# waga_can.net
KiCad netlist of a schematic drawn in EAGLE
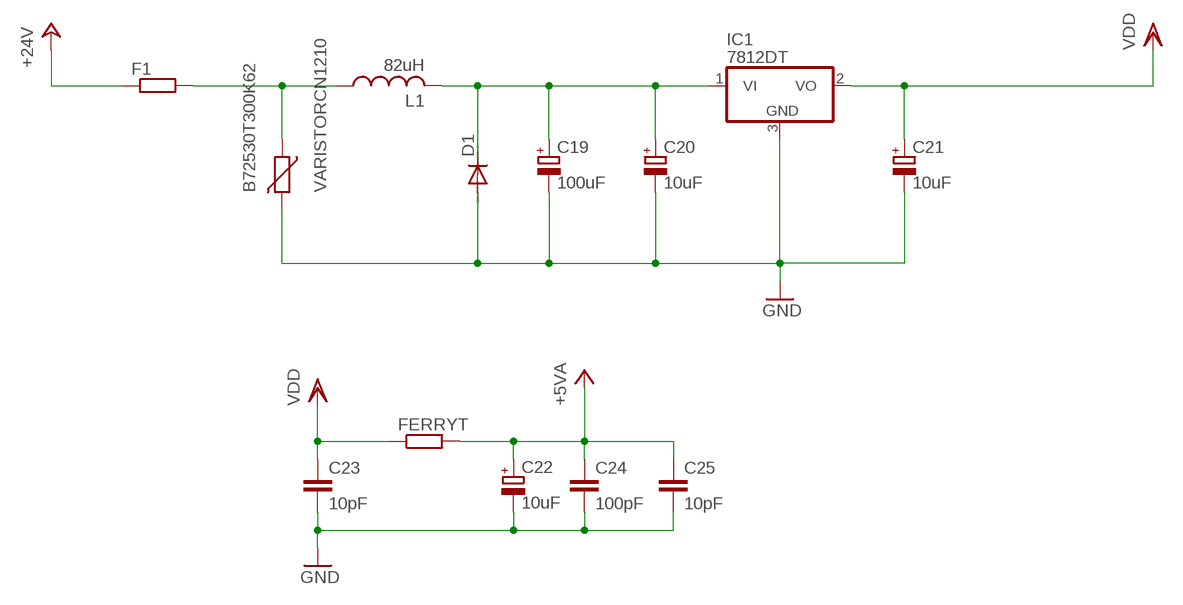
[diagram p0: schematic, sheet 1]
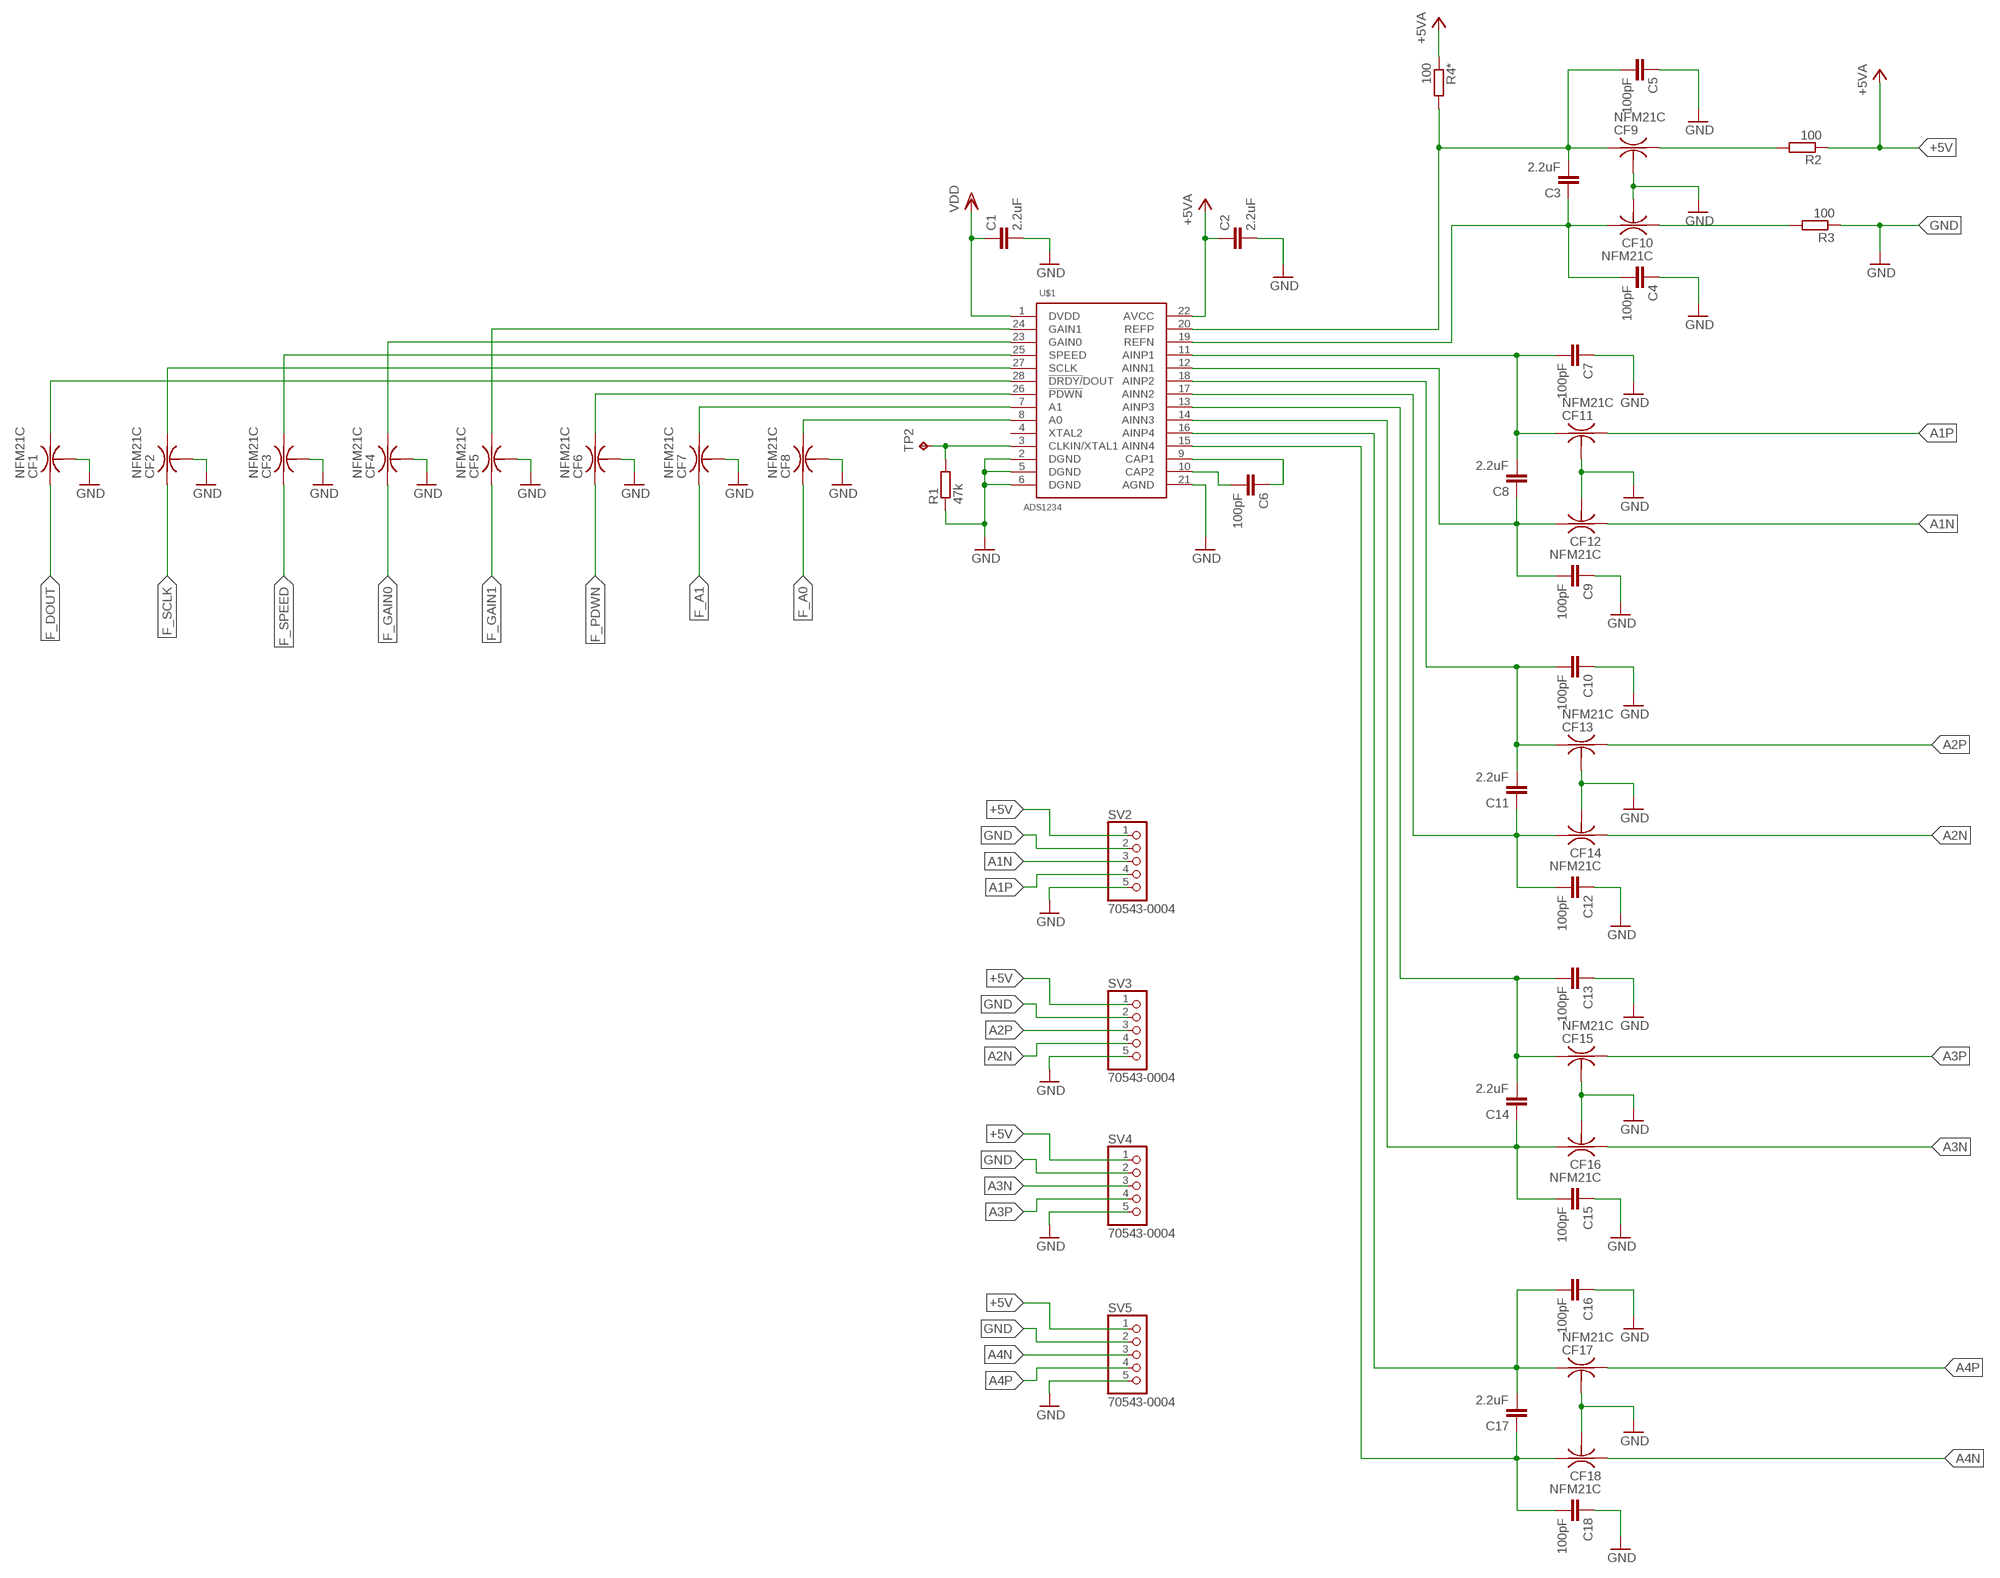
[diagram p1: schematic, sheet 2, part 1 of 2]
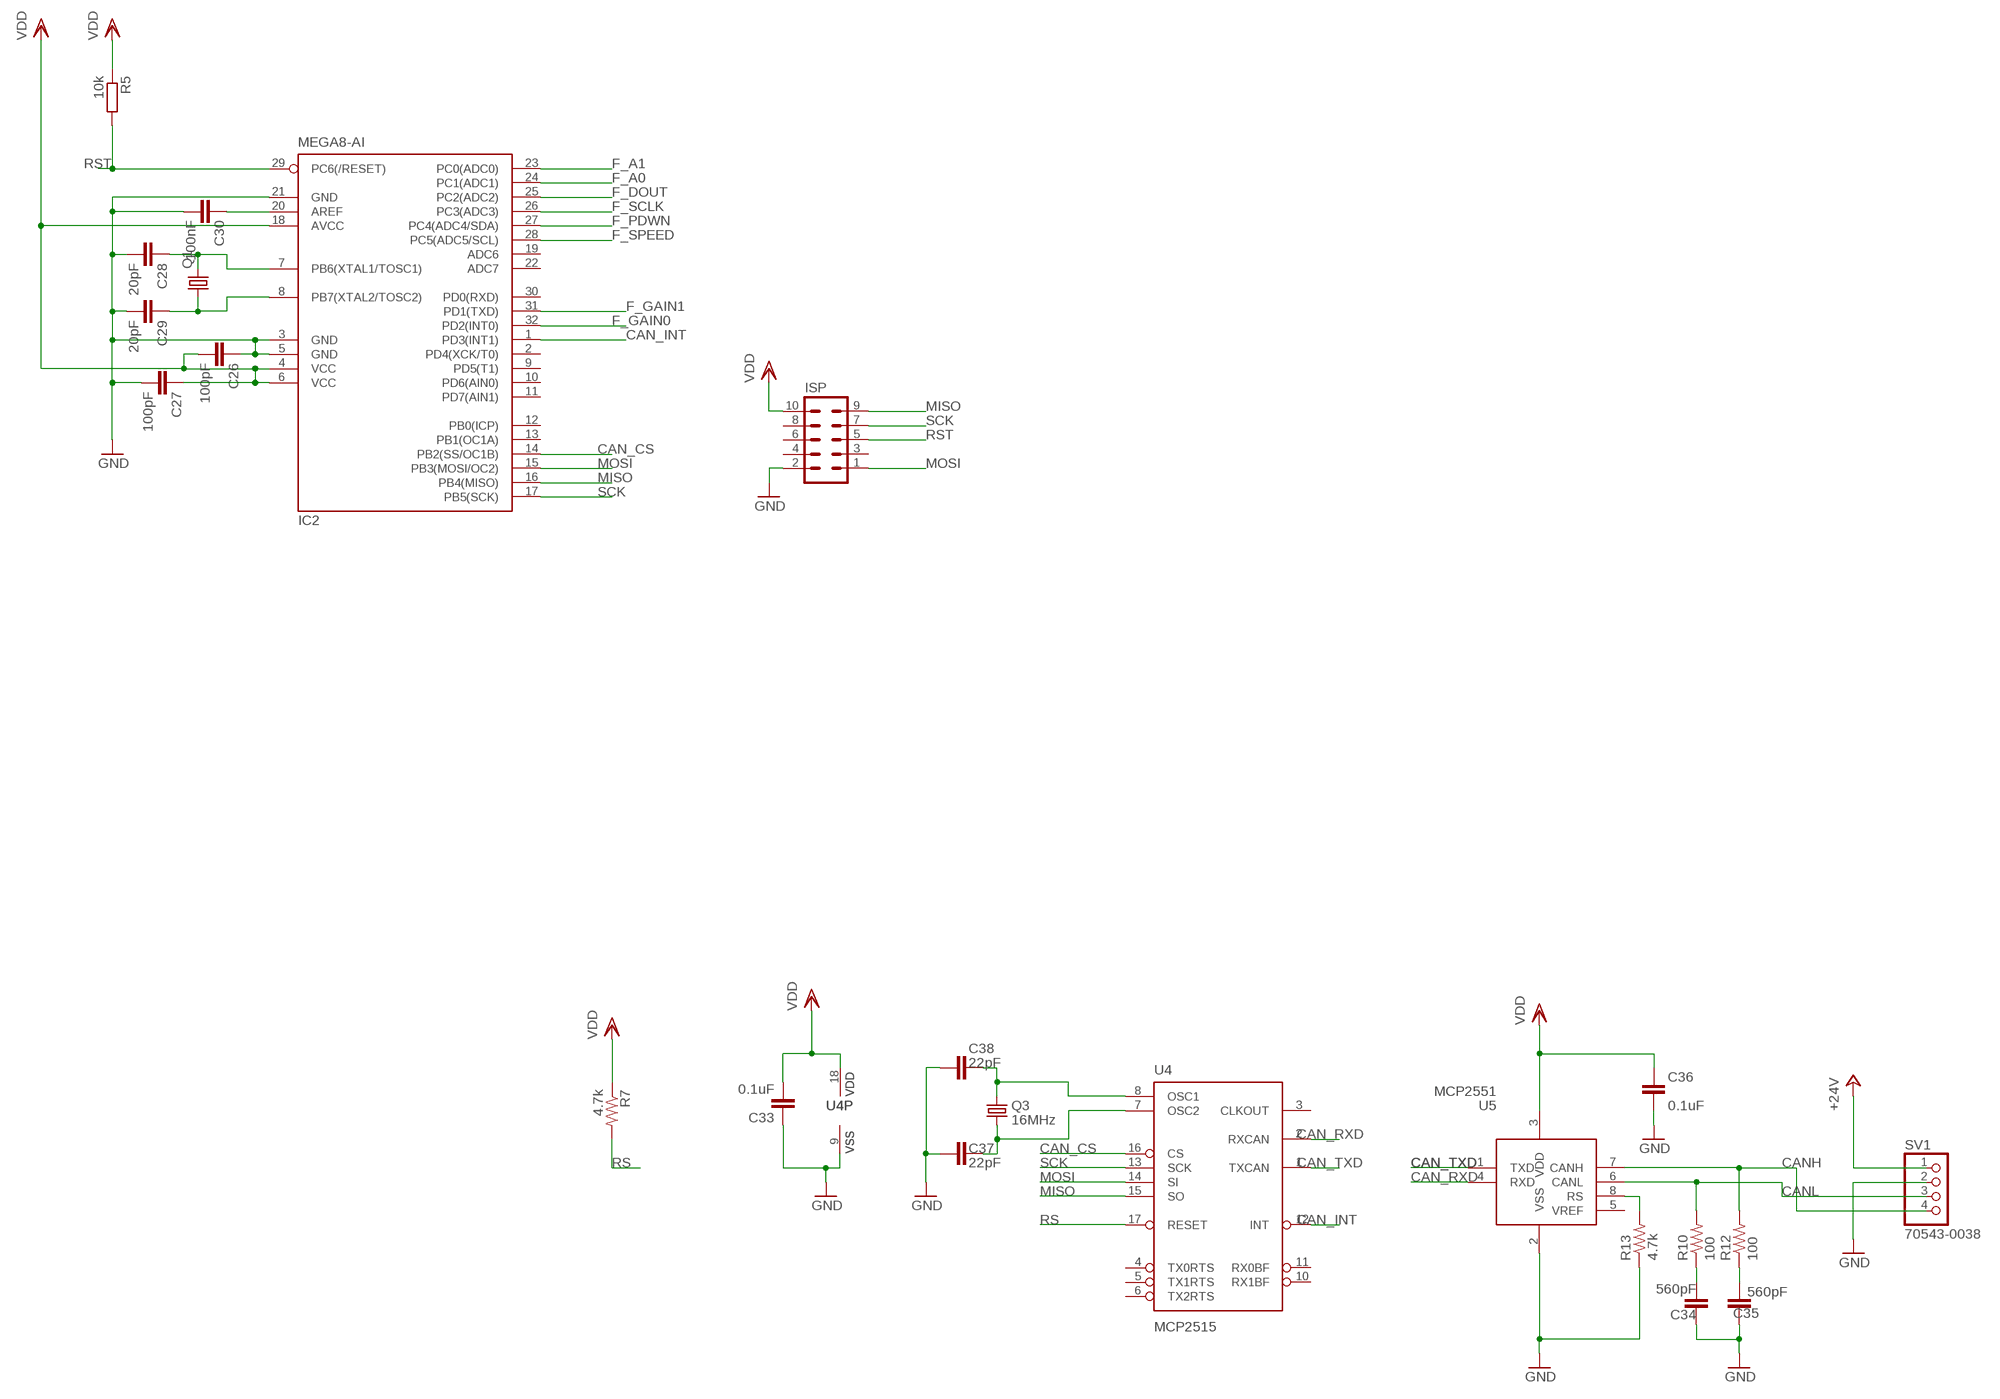
[diagram p2: schematic, sheet 2, part 2 of 2]

(export (version "E")
  (design (tool "Eeschema 10.0.6"))
  (components
    (comp (ref "B72530T300K62")
      (value "VARISTORCN1210")
      (footprint "eagle-import:CT_CN1210")
      (libsource (lib "eagle-import") (part "VARISTORCN1210"))
    )
    (comp (ref "C19")
      (value "100uF")
      (footprint "eagle-import:153CLV-0810")
      (libsource (lib "eagle-import") (part "CPOL-EU153CLV-0810"))
    )
    (comp (ref "C20")
      (value "10uF")
      (footprint "eagle-import:153CLV-0605")
      (libsource (lib "eagle-import") (part "CPOL-EU153CLV-0605"))
    )
    (comp (ref "C21")
      (value "10uF")
      (footprint "eagle-import:153CLV-0605")
      (libsource (lib "eagle-import") (part "CPOL-EU153CLV-0605"))
    )
    (comp (ref "C22")
      (value "10uF")
      (footprint "eagle-import:153CLV-0605")
      (libsource (lib "eagle-import") (part "CPOL-EU153CLV-0605"))
    )
    (comp (ref "C23")
      (value "10pF")
      (footprint "eagle-import:C0805")
      (libsource (lib "eagle-import") (part "C-EUC0805"))
    )
    (comp (ref "C24")
      (value "100pF")
      (footprint "eagle-import:C0805")
      (libsource (lib "eagle-import") (part "C-EUC0805"))
    )
    (comp (ref "C25")
      (value "10pF")
      (footprint "eagle-import:C0805")
      (libsource (lib "eagle-import") (part "C-EUC0805"))
    )
    (comp (ref "D1")
      (value "DIODE-SMB")
      (footprint "eagle-import:SMB")
      (libsource (lib "eagle-import") (part "DIODE-SMB"))
    )
    (comp (ref "F1")
      (value "R-EU_1812X7R")
      (footprint "eagle-import:1812X7R")
      (libsource (lib "eagle-import") (part "R-EU_1812X7R"))
    )
    (comp (ref "FERRYT")
      (value "R-EU_M0805")
      (footprint "eagle-import:M0805")
      (libsource (lib "eagle-import") (part "R-EU_M0805"))
    )
    (comp (ref "IC1")
      (value "7812DT")
      (footprint "eagle-import:TO252")
      (libsource (lib "eagle-import") (part "78DT12"))
    )
    (comp (ref "L1")
      (value "82uH")
      (footprint "eagle-import:L4532P")
      (libsource (lib "eagle-import") (part "L-USL4532P"))
    )
    (comp (ref "C1")
      (value "2.2uF")
      (footprint "eagle-import:C0805K")
      (libsource (lib "eagle-import") (part "C-EUC0805K"))
    )
    (comp (ref "C2")
      (value "2.2uF")
      (footprint "eagle-import:C0805K")
      (libsource (lib "eagle-import") (part "C-EUC0805K"))
    )
    (comp (ref "C3")
      (value "2.2uF")
      (footprint "eagle-import:C0805K")
      (libsource (lib "eagle-import") (part "C-EUC0805K"))
    )
    (comp (ref "C4")
      (value "100pF")
      (footprint "eagle-import:C0603")
      (libsource (lib "eagle-import") (part "C-EUC0603"))
    )
    (comp (ref "C5")
      (value "100pF")
      (footprint "eagle-import:C0603")
      (libsource (lib "eagle-import") (part "C-EUC0603"))
    )
    (comp (ref "C6")
      (value "100pF")
      (footprint "eagle-import:C0603")
      (libsource (lib "eagle-import") (part "C-EUC0603"))
    )
    (comp (ref "C7")
      (value "100pF")
      (footprint "eagle-import:C0603")
      (libsource (lib "eagle-import") (part "C-EUC0603"))
    )
    (comp (ref "C8")
      (value "2.2uF")
      (footprint "eagle-import:C0805K")
      (libsource (lib "eagle-import") (part "C-EUC0805K"))
    )
    (comp (ref "C9")
      (value "100pF")
      (footprint "eagle-import:C0603")
      (libsource (lib "eagle-import") (part "C-EUC0603"))
    )
    (comp (ref "C10")
      (value "100pF")
      (footprint "eagle-import:C0603")
      (libsource (lib "eagle-import") (part "C-EUC0603"))
    )
    (comp (ref "C11")
      (value "2.2uF")
      (footprint "eagle-import:C0805K")
      (libsource (lib "eagle-import") (part "C-EUC0805K"))
    )
    (comp (ref "C12")
      (value "100pF")
      (footprint "eagle-import:C0603")
      (libsource (lib "eagle-import") (part "C-EUC0603"))
    )
    (comp (ref "C13")
      (value "100pF")
      (footprint "eagle-import:C0603")
      (libsource (lib "eagle-import") (part "C-EUC0603"))
    )
    (comp (ref "C14")
      (value "2.2uF")
      (footprint "eagle-import:C0805K")
      (libsource (lib "eagle-import") (part "C-EUC0805K"))
    )
    (comp (ref "C15")
      (value "100pF")
      (footprint "eagle-import:C0603")
      (libsource (lib "eagle-import") (part "C-EUC0603"))
    )
    (comp (ref "C16")
      (value "100pF")
      (footprint "eagle-import:C0603")
      (libsource (lib "eagle-import") (part "C-EUC0603"))
    )
    (comp (ref "C17")
      (value "2.2uF")
      (footprint "eagle-import:C0805K")
      (libsource (lib "eagle-import") (part "C-EUC0805K"))
    )
    (comp (ref "C18")
      (value "100pF")
      (footprint "eagle-import:C0603")
      (libsource (lib "eagle-import") (part "C-EUC0603"))
    )
    (comp (ref "C26")
      (value "100pF")
      (footprint "eagle-import:C0805K")
      (libsource (lib "eagle-import") (part "C-EUC0805K"))
    )
    (comp (ref "C27")
      (value "100pF")
      (footprint "eagle-import:C0805K")
      (libsource (lib "eagle-import") (part "C-EUC0805K"))
    )
    (comp (ref "C28")
      (value "20pF")
      (footprint "eagle-import:C0805K")
      (libsource (lib "eagle-import") (part "C-EUC0805K"))
    )
    (comp (ref "C29")
      (value "20pF")
      (footprint "eagle-import:C0805K")
      (libsource (lib "eagle-import") (part "C-EUC0805K"))
    )
    (comp (ref "C30")
      (value "100nF")
      (footprint "eagle-import:C0805K")
      (libsource (lib "eagle-import") (part "C-EUC0805K"))
    )
    (comp (ref "C33")
      (value "0.1uF")
      (footprint "eagle-import:0603-CAP")
      (libsource (lib "eagle-import") (part "CAP0603-CAP"))
    )
    (comp (ref "C34")
      (value "560pF")
      (footprint "eagle-import:0603-CAP")
      (libsource (lib "eagle-import") (part "CAP0603-CAP"))
    )
    (comp (ref "C35")
      (value "560pF")
      (footprint "eagle-import:0603-CAP")
      (libsource (lib "eagle-import") (part "CAP0603-CAP"))
    )
    (comp (ref "C36")
      (value "0.1uF")
      (footprint "eagle-import:0603-CAP")
      (libsource (lib "eagle-import") (part "CAP0603-CAP"))
    )
    (comp (ref "C37")
      (value "22pF")
      (footprint "eagle-import:0603-CAP")
      (libsource (lib "eagle-import") (part "CAP0603-CAP"))
    )
    (comp (ref "C38")
      (value "22pF")
      (footprint "eagle-import:0603-CAP")
      (libsource (lib "eagle-import") (part "CAP0603-CAP"))
    )
    (comp (ref "CF1")
      (value "NFM21C")
      (footprint "eagle-import:NFM21C")
      (fields (field (name "MPN") "NFM21CC102R1H3D"))
      (libsource (lib "eagle-import") (part "NFM21C"))
    )
    (comp (ref "CF2")
      (value "NFM21C")
      (footprint "eagle-import:NFM21C")
      (fields (field (name "MPN") "NFM21CC102R1H3D"))
      (libsource (lib "eagle-import") (part "NFM21C"))
    )
    (comp (ref "CF3")
      (value "NFM21C")
      (footprint "eagle-import:NFM21C")
      (fields (field (name "MPN") "NFM21CC102R1H3D"))
      (libsource (lib "eagle-import") (part "NFM21C"))
    )
    (comp (ref "CF4")
      (value "NFM21C")
      (footprint "eagle-import:NFM21C")
      (fields (field (name "MPN") "NFM21CC102R1H3D"))
      (libsource (lib "eagle-import") (part "NFM21C"))
    )
    (comp (ref "CF5")
      (value "NFM21C")
      (footprint "eagle-import:NFM21C")
      (fields (field (name "MPN") "NFM21CC102R1H3D"))
      (libsource (lib "eagle-import") (part "NFM21C"))
    )
    (comp (ref "CF6")
      (value "NFM21C")
      (footprint "eagle-import:NFM21C")
      (fields (field (name "MPN") "NFM21CC102R1H3D"))
      (libsource (lib "eagle-import") (part "NFM21C"))
    )
    (comp (ref "CF7")
      (value "NFM21C")
      (footprint "eagle-import:NFM21C")
      (fields (field (name "MPN") "NFM21CC102R1H3D"))
      (libsource (lib "eagle-import") (part "NFM21C"))
    )
    (comp (ref "CF8")
      (value "NFM21C")
      (footprint "eagle-import:NFM21C")
      (fields (field (name "MPN") "NFM21CC102R1H3D"))
      (libsource (lib "eagle-import") (part "NFM21C"))
    )
    (comp (ref "CF9")
      (value "NFM21C")
      (footprint "eagle-import:NFM21C")
      (fields (field (name "MPN") "NFM21CC102R1H3D"))
      (libsource (lib "eagle-import") (part "NFM21C"))
    )
    (comp (ref "CF10")
      (value "NFM21C")
      (footprint "eagle-import:NFM21C")
      (fields (field (name "MPN") "NFM21CC102R1H3D"))
      (libsource (lib "eagle-import") (part "NFM21C"))
    )
    (comp (ref "CF11")
      (value "NFM21C")
      (footprint "eagle-import:NFM21C")
      (fields (field (name "MPN") "NFM21CC102R1H3D"))
      (libsource (lib "eagle-import") (part "NFM21C"))
    )
    (comp (ref "CF12")
      (value "NFM21C")
      (footprint "eagle-import:NFM21C")
      (fields (field (name "MPN") "NFM21CC102R1H3D"))
      (libsource (lib "eagle-import") (part "NFM21C"))
    )
    (comp (ref "CF13")
      (value "NFM21C")
      (footprint "eagle-import:NFM21C")
      (fields (field (name "MPN") "NFM21CC102R1H3D"))
      (libsource (lib "eagle-import") (part "NFM21C"))
    )
    (comp (ref "CF14")
      (value "NFM21C")
      (footprint "eagle-import:NFM21C")
      (fields (field (name "MPN") "NFM21CC102R1H3D"))
      (libsource (lib "eagle-import") (part "NFM21C"))
    )
    (comp (ref "CF15")
      (value "NFM21C")
      (footprint "eagle-import:NFM21C")
      (fields (field (name "MPN") "NFM21CC102R1H3D"))
      (libsource (lib "eagle-import") (part "NFM21C"))
    )
    (comp (ref "CF16")
      (value "NFM21C")
      (footprint "eagle-import:NFM21C")
      (fields (field (name "MPN") "NFM21CC102R1H3D"))
      (libsource (lib "eagle-import") (part "NFM21C"))
    )
    (comp (ref "CF17")
      (value "NFM21C")
      (footprint "eagle-import:NFM21C")
      (fields (field (name "MPN") "NFM21CC102R1H3D"))
      (libsource (lib "eagle-import") (part "NFM21C"))
    )
    (comp (ref "CF18")
      (value "NFM21C")
      (footprint "eagle-import:NFM21C")
      (fields (field (name "MPN") "NFM21CC102R1H3D"))
      (libsource (lib "eagle-import") (part "NFM21C"))
    )
    (comp (ref "IC2")
      (value "MEGA8-AI")
      (footprint "eagle-import:TQFP32-08")
      (fields (field (name "MPN") "ATMEGA8-16AU"))
      (libsource (lib "eagle-import") (part "MEGA8-AI"))
    )
    (comp (ref "ISP")
      (value "ML10")
      (footprint "eagle-import:ML10")
      (libsource (lib "eagle-import") (part "ML10"))
    )
    (comp (ref "Q1")
      (value "CRYSTALCTS406")
      (footprint "eagle-import:CTS406")
      (libsource (lib "eagle-import") (part "CRYSTALCTS406"))
    )
    (comp (ref "Q3")
      (value "16MHz")
      (footprint "eagle-import:CRYSTAL-SMD-5X3")
      (libsource (lib "eagle-import") (part "CRYSTAL5X3"))
    )
    (comp (ref "R1")
      (value "47k")
      (footprint "eagle-import:R0805")
      (libsource (lib "eagle-import") (part "R-EU_R0805"))
    )
    (comp (ref "R2")
      (value "100")
      (footprint "eagle-import:R0805")
      (libsource (lib "eagle-import") (part "R-EU_R0805"))
    )
    (comp (ref "R3")
      (value "100")
      (footprint "eagle-import:R0805")
      (libsource (lib "eagle-import") (part "R-EU_R0805"))
    )
    (comp (ref "R4*")
      (value "100")
      (footprint "eagle-import:R0805")
      (libsource (lib "eagle-import") (part "R-EU_R0805"))
    )
    (comp (ref "R5")
      (value "10k")
      (footprint "eagle-import:R0805")
      (libsource (lib "eagle-import") (part "R-EU_R0805"))
    )
    (comp (ref "R7")
      (value "4.7k")
      (footprint "eagle-import:0603-RES")
      (libsource (lib "eagle-import") (part "RESISTOR0603-RES"))
    )
    (comp (ref "R10")
      (value "100")
      (footprint "eagle-import:0603-RES")
      (libsource (lib "eagle-import") (part "RESISTOR0603-RES"))
    )
    (comp (ref "R12")
      (value "100")
      (footprint "eagle-import:0603-RES")
      (libsource (lib "eagle-import") (part "RESISTOR0603-RES"))
    )
    (comp (ref "R13")
      (value "4.7k")
      (footprint "eagle-import:0603-RES")
      (libsource (lib "eagle-import") (part "RESISTOR0603-RES"))
    )
    (comp (ref "SV1")
      (value "70543-0038")
      (footprint "eagle-import:70543-0038")
      (libsource (lib "eagle-import") (part "70543-0038"))
    )
    (comp (ref "SV2")
      (value "70543-0004")
      (footprint "eagle-import:70543-0004")
      (libsource (lib "eagle-import") (part "70543-0004"))
    )
    (comp (ref "SV3")
      (value "70543-0004")
      (footprint "eagle-import:70543-0004")
      (libsource (lib "eagle-import") (part "70543-0004"))
    )
    (comp (ref "SV4")
      (value "70543-0004")
      (footprint "eagle-import:70543-0004")
      (libsource (lib "eagle-import") (part "70543-0004"))
    )
    (comp (ref "SV5")
      (value "70543-0004")
      (footprint "eagle-import:70543-0004")
      (libsource (lib "eagle-import") (part "70543-0004"))
    )
    (comp (ref "TP2")
      (value "TPTP06R")
      (footprint "eagle-import:TP06R")
      (libsource (lib "eagle-import") (part "TPTP06R"))
    )
    (comp (ref "U$1")
      (value "ADS1234")
      (footprint "eagle-import:TSSOP-28")
      (libsource (lib "eagle-import") (part "ADS1234"))
    )
    (comp (ref "U4")
      (value "MCP2515")
      (footprint "eagle-import:SO-18W")
      (libsource (lib "eagle-import") (part "MCP2510SO"))
    )
    (comp (ref "U5")
      (value "MCP2551")
      (footprint "eagle-import:SO-08M")
      (libsource (lib "eagle-import") (part "MCP2551"))
    )
  )
  (nets
    (net (code "1") (name "+5V") (class "Default")
      (node (ref "C2") (pin "1") (pinfunction "1_1") (pintype "passive"))
      (node (ref "C22") (pin "+") (pinfunction "+_+") (pintype "passive"))
      (node (ref "C24") (pin "1") (pinfunction "1_1") (pintype "passive"))
      (node (ref "C25") (pin "1") (pinfunction "1_1") (pintype "passive"))
      (node (ref "FERRYT") (pin "2") (pinfunction "2_2") (pintype "passive"))
      (node (ref "R2") (pin "1") (pinfunction "1_1") (pintype "passive"))
      (node (ref "R4*") (pin "1") (pinfunction "1_1") (pintype "passive"))
      (node (ref "SV2") (pin "1") (pinfunction "1_1") (pintype "passive"))
      (node (ref "SV3") (pin "1") (pinfunction "1_1") (pintype "passive"))
      (node (ref "SV4") (pin "1") (pinfunction "1_1") (pintype "passive"))
      (node (ref "SV5") (pin "1") (pinfunction "1_1") (pintype "passive"))
      (node (ref "U$1") (pin "22") (pinfunction "AVCC_22") (pintype "bidirectional"))
    )
    (net (code "2") (name "+24V") (class "Default")
      (node (ref "F1") (pin "1") (pinfunction "1_1") (pintype "passive"))
      (node (ref "SV1") (pin "1") (pinfunction "1_1") (pintype "passive"))
    )
    (net (code "3") (name "A1N") (class "Default")
      (node (ref "CF12") (pin "1") (pinfunction "1_1") (pintype "passive"))
      (node (ref "SV2") (pin "3") (pinfunction "3_3") (pintype "passive"))
    )
    (net (code "4") (name "A1P") (class "Default")
      (node (ref "CF11") (pin "3") (pinfunction "3_3") (pintype "passive"))
      (node (ref "SV2") (pin "4") (pinfunction "4_4") (pintype "passive"))
    )
    (net (code "5") (name "A2N") (class "Default")
      (node (ref "CF14") (pin "1") (pinfunction "1_1") (pintype "passive"))
      (node (ref "SV3") (pin "4") (pinfunction "4_4") (pintype "passive"))
    )
    (net (code "6") (name "A2P") (class "Default")
      (node (ref "CF13") (pin "3") (pinfunction "3_3") (pintype "passive"))
      (node (ref "SV3") (pin "3") (pinfunction "3_3") (pintype "passive"))
    )
    (net (code "7") (name "A3N") (class "Default")
      (node (ref "CF16") (pin "1") (pinfunction "1_1") (pintype "passive"))
      (node (ref "SV4") (pin "3") (pinfunction "3_3") (pintype "passive"))
    )
    (net (code "8") (name "A3P") (class "Default")
      (node (ref "CF15") (pin "3") (pinfunction "3_3") (pintype "passive"))
      (node (ref "SV4") (pin "4") (pinfunction "4_4") (pintype "passive"))
    )
    (net (code "9") (name "A4N") (class "Default")
      (node (ref "CF18") (pin "1") (pinfunction "1_1") (pintype "passive"))
      (node (ref "SV5") (pin "3") (pinfunction "3_3") (pintype "passive"))
    )
    (net (code "10") (name "A4P") (class "Default")
      (node (ref "CF17") (pin "3") (pinfunction "3_3") (pintype "passive"))
      (node (ref "SV5") (pin "4") (pinfunction "4_4") (pintype "passive"))
    )
    (net (code "11") (name "CANH") (class "Default")
      (node (ref "R12") (pin "2") (pinfunction "2_2") (pintype "passive"))
      (node (ref "SV1") (pin "4") (pinfunction "4_4") (pintype "passive"))
      (node (ref "U5") (pin "7") (pinfunction "CANH_7") (pintype "bidirectional"))
    )
    (net (code "12") (name "CANL") (class "Default")
      (node (ref "R10") (pin "2") (pinfunction "2_2") (pintype "passive"))
      (node (ref "SV1") (pin "3") (pinfunction "3_3") (pintype "passive"))
      (node (ref "U5") (pin "6") (pinfunction "CANL_6") (pintype "bidirectional"))
    )
    (net (code "13") (name "CAN_CS") (class "Default")
      (node (ref "IC2") (pin "14") (pinfunction "PB2(SS/OC1B)_14") (pintype "bidirectional"))
      (node (ref "U4") (pin "16") (pinfunction "CS_16") (pintype "input"))
    )
    (net (code "14") (name "CAN_INT") (class "Default")
      (node (ref "IC2") (pin "1") (pinfunction "PD3(INT1)_1") (pintype "bidirectional"))
      (node (ref "U4") (pin "12") (pinfunction "INT_12") (pintype "output"))
    )
    (net (code "15") (name "CAN_RXD") (class "Default")
      (node (ref "U4") (pin "2") (pinfunction "RXCAN_2") (pintype "input"))
      (node (ref "U5") (pin "4") (pinfunction "RXD_4") (pintype "bidirectional"))
    )
    (net (code "16") (name "CAN_TXD") (class "Default")
      (node (ref "U4") (pin "1") (pinfunction "TXCAN_1") (pintype "output"))
      (node (ref "U5") (pin "1") (pinfunction "TXD_1") (pintype "bidirectional"))
    )
    (net (code "17") (name "F_A0") (class "Default")
      (node (ref "CF8") (pin "1") (pinfunction "1_1") (pintype "passive"))
      (node (ref "IC2") (pin "24") (pinfunction "PC1(ADC1)_24") (pintype "bidirectional"))
    )
    (net (code "18") (name "F_A1") (class "Default")
      (node (ref "CF7") (pin "1") (pinfunction "1_1") (pintype "passive"))
      (node (ref "IC2") (pin "23") (pinfunction "PC0(ADC0)_23") (pintype "bidirectional"))
    )
    (net (code "19") (name "F_DOUT") (class "Default")
      (node (ref "CF1") (pin "1") (pinfunction "1_1") (pintype "passive"))
      (node (ref "IC2") (pin "25") (pinfunction "PC2(ADC2)_25") (pintype "bidirectional"))
    )
    (net (code "20") (name "F_GAIN0") (class "Default")
      (node (ref "CF4") (pin "1") (pinfunction "1_1") (pintype "passive"))
      (node (ref "IC2") (pin "32") (pinfunction "PD2(INT0)_32") (pintype "bidirectional"))
    )
    (net (code "21") (name "F_GAIN1") (class "Default")
      (node (ref "CF5") (pin "1") (pinfunction "1_1") (pintype "passive"))
      (node (ref "IC2") (pin "31") (pinfunction "PD1(TXD)_31") (pintype "bidirectional"))
    )
    (net (code "22") (name "F_PDWN") (class "Default")
      (node (ref "CF6") (pin "1") (pinfunction "1_1") (pintype "passive"))
      (node (ref "IC2") (pin "27") (pinfunction "PC4(ADC4/SDA)_27") (pintype "bidirectional"))
    )
    (net (code "23") (name "F_SCLK") (class "Default")
      (node (ref "CF2") (pin "1") (pinfunction "1_1") (pintype "passive"))
      (node (ref "IC2") (pin "26") (pinfunction "PC3(ADC3)_26") (pintype "bidirectional"))
    )
    (net (code "24") (name "F_SPEED") (class "Default")
      (node (ref "CF3") (pin "1") (pinfunction "1_1") (pintype "passive"))
      (node (ref "IC2") (pin "28") (pinfunction "PC5(ADC5/SCL)_28") (pintype "bidirectional"))
    )
    (net (code "25") (name "GND") (class "Default")
      (node (ref "B72530T300K62") (pin "2") (pinfunction "2_2") (pintype "passive"))
      (node (ref "C1") (pin "2") (pinfunction "2_2") (pintype "passive"))
      (node (ref "C10") (pin "1") (pinfunction "1_1") (pintype "passive"))
      (node (ref "C12") (pin "1") (pinfunction "1_1") (pintype "passive"))
      (node (ref "C13") (pin "1") (pinfunction "1_1") (pintype "passive"))
      (node (ref "C15") (pin "1") (pinfunction "1_1") (pintype "passive"))
      (node (ref "C16") (pin "1") (pinfunction "1_1") (pintype "passive"))
      (node (ref "C18") (pin "1") (pinfunction "1_1") (pintype "passive"))
      (node (ref "C19") (pin "-") (pinfunction "-_-") (pintype "passive"))
      (node (ref "C2") (pin "2") (pinfunction "2_2") (pintype "passive"))
      (node (ref "C20") (pin "-") (pinfunction "-_-") (pintype "passive"))
      (node (ref "C21") (pin "-") (pinfunction "-_-") (pintype "passive"))
      (node (ref "C22") (pin "-") (pinfunction "-_-") (pintype "passive"))
      (node (ref "C23") (pin "2") (pinfunction "2_2") (pintype "passive"))
      (node (ref "C24") (pin "2") (pinfunction "2_2") (pintype "passive"))
      (node (ref "C25") (pin "2") (pinfunction "2_2") (pintype "passive"))
      (node (ref "C26") (pin "1") (pinfunction "1_1") (pintype "passive"))
      (node (ref "C27") (pin "2") (pinfunction "2_2") (pintype "passive"))
      (node (ref "C28") (pin "2") (pinfunction "2_2") (pintype "passive"))
      (node (ref "C29") (pin "2") (pinfunction "2_2") (pintype "passive"))
      (node (ref "C30") (pin "2") (pinfunction "2_2") (pintype "passive"))
      (node (ref "C33") (pin "1") (pinfunction "1_1") (pintype "passive"))
      (node (ref "C34") (pin "1") (pinfunction "1_1") (pintype "passive"))
      (node (ref "C35") (pin "1") (pinfunction "1_1") (pintype "passive"))
      (node (ref "C36") (pin "1") (pinfunction "1_1") (pintype "passive"))
      (node (ref "C37") (pin "1") (pinfunction "1_1") (pintype "passive"))
      (node (ref "C38") (pin "1") (pinfunction "1_1") (pintype "passive"))
      (node (ref "C4") (pin "1") (pinfunction "1_1") (pintype "passive"))
      (node (ref "C5") (pin "1") (pinfunction "1_1") (pintype "passive"))
      (node (ref "C7") (pin "1") (pinfunction "1_1") (pintype "passive"))
      (node (ref "C9") (pin "1") (pinfunction "1_1") (pintype "passive"))
      (node (ref "CF1") (pin "2@1") (pinfunction "2_2@1") (pintype "passive"))
      (node (ref "CF1") (pin "2@2") (pinfunction "2_2@2") (pintype "passive"))
      (node (ref "CF10") (pin "2@1") (pinfunction "2_2@1") (pintype "passive"))
      (node (ref "CF10") (pin "2@2") (pinfunction "2_2@2") (pintype "passive"))
      (node (ref "CF11") (pin "2@1") (pinfunction "2_2@1") (pintype "passive"))
      (node (ref "CF11") (pin "2@2") (pinfunction "2_2@2") (pintype "passive"))
      (node (ref "CF12") (pin "2@1") (pinfunction "2_2@1") (pintype "passive"))
      (node (ref "CF12") (pin "2@2") (pinfunction "2_2@2") (pintype "passive"))
      (node (ref "CF13") (pin "2@1") (pinfunction "2_2@1") (pintype "passive"))
      (node (ref "CF13") (pin "2@2") (pinfunction "2_2@2") (pintype "passive"))
      (node (ref "CF14") (pin "2@1") (pinfunction "2_2@1") (pintype "passive"))
      (node (ref "CF14") (pin "2@2") (pinfunction "2_2@2") (pintype "passive"))
      (node (ref "CF15") (pin "2@1") (pinfunction "2_2@1") (pintype "passive"))
      (node (ref "CF15") (pin "2@2") (pinfunction "2_2@2") (pintype "passive"))
      (node (ref "CF16") (pin "2@1") (pinfunction "2_2@1") (pintype "passive"))
      (node (ref "CF16") (pin "2@2") (pinfunction "2_2@2") (pintype "passive"))
      (node (ref "CF17") (pin "2@1") (pinfunction "2_2@1") (pintype "passive"))
      (node (ref "CF17") (pin "2@2") (pinfunction "2_2@2") (pintype "passive"))
      (node (ref "CF18") (pin "2@1") (pinfunction "2_2@1") (pintype "passive"))
      (node (ref "CF18") (pin "2@2") (pinfunction "2_2@2") (pintype "passive"))
      (node (ref "CF2") (pin "2@1") (pinfunction "2_2@1") (pintype "passive"))
      (node (ref "CF2") (pin "2@2") (pinfunction "2_2@2") (pintype "passive"))
      (node (ref "CF3") (pin "2@1") (pinfunction "2_2@1") (pintype "passive"))
      (node (ref "CF3") (pin "2@2") (pinfunction "2_2@2") (pintype "passive"))
      (node (ref "CF4") (pin "2@1") (pinfunction "2_2@1") (pintype "passive"))
      (node (ref "CF4") (pin "2@2") (pinfunction "2_2@2") (pintype "passive"))
      (node (ref "CF5") (pin "2@1") (pinfunction "2_2@1") (pintype "passive"))
      (node (ref "CF5") (pin "2@2") (pinfunction "2_2@2") (pintype "passive"))
      (node (ref "CF6") (pin "2@1") (pinfunction "2_2@1") (pintype "passive"))
      (node (ref "CF6") (pin "2@2") (pinfunction "2_2@2") (pintype "passive"))
      (node (ref "CF7") (pin "2@1") (pinfunction "2_2@1") (pintype "passive"))
      (node (ref "CF7") (pin "2@2") (pinfunction "2_2@2") (pintype "passive"))
      (node (ref "CF8") (pin "2@1") (pinfunction "2_2@1") (pintype "passive"))
      (node (ref "CF8") (pin "2@2") (pinfunction "2_2@2") (pintype "passive"))
      (node (ref "CF9") (pin "2@1") (pinfunction "2_2@1") (pintype "passive"))
      (node (ref "CF9") (pin "2@2") (pinfunction "2_2@2") (pintype "passive"))
      (node (ref "D1") (pin "A") (pinfunction "A_A") (pintype "passive"))
      (node (ref "IC1") (pin "3") (pinfunction "GND_3") (pintype "passive"))
      (node (ref "IC2") (pin "21") (pinfunction "GND_21") (pintype "power_in"))
      (node (ref "IC2") (pin "3") (pinfunction "GND_3") (pintype "power_in"))
      (node (ref "IC2") (pin "5") (pinfunction "GND_5") (pintype "power_in"))
      (node (ref "ISP") (pin "2") (pinfunction "2_2") (pintype "passive"))
      (node (ref "R1") (pin "1") (pinfunction "1_1") (pintype "passive"))
      (node (ref "R13") (pin "1") (pinfunction "1_1") (pintype "passive"))
      (node (ref "R3") (pin "1") (pinfunction "1_1") (pintype "passive"))
      (node (ref "SV1") (pin "2") (pinfunction "2_2") (pintype "passive"))
      (node (ref "SV2") (pin "2") (pinfunction "2_2") (pintype "passive"))
      (node (ref "SV2") (pin "5") (pinfunction "5_5") (pintype "passive"))
      (node (ref "SV3") (pin "2") (pinfunction "2_2") (pintype "passive"))
      (node (ref "SV3") (pin "5") (pinfunction "5_5") (pintype "passive"))
      (node (ref "SV4") (pin "2") (pinfunction "2_2") (pintype "passive"))
      (node (ref "SV4") (pin "5") (pinfunction "5_5") (pintype "passive"))
      (node (ref "SV5") (pin "2") (pinfunction "2_2") (pintype "passive"))
      (node (ref "SV5") (pin "5") (pinfunction "5_5") (pintype "passive"))
      (node (ref "U$1") (pin "2") (pinfunction "DGND_2") (pintype "bidirectional"))
      (node (ref "U$1") (pin "21") (pinfunction "AGND_21") (pintype "bidirectional"))
      (node (ref "U$1") (pin "5") (pinfunction "DGND_5") (pintype "bidirectional"))
      (node (ref "U$1") (pin "6") (pinfunction "DGND_6") (pintype "bidirectional"))
      (node (ref "U4") (pin "9") (pinfunction "VSS_9") (pintype "power_in"))
      (node (ref "U5") (pin "2") (pinfunction "VSS_2") (pintype "power_in"))
    )
    (net (code "26") (name "MISO") (class "Default")
      (node (ref "IC2") (pin "16") (pinfunction "PB4(MISO)_16") (pintype "bidirectional"))
      (node (ref "ISP") (pin "9") (pinfunction "9_9") (pintype "passive"))
      (node (ref "U4") (pin "15") (pinfunction "SO_15") (pintype "output"))
    )
    (net (code "27") (name "MOSI") (class "Default")
      (node (ref "IC2") (pin "15") (pinfunction "PB3(MOSI/OC2)_15") (pintype "bidirectional"))
      (node (ref "ISP") (pin "1") (pinfunction "1_1") (pintype "passive"))
      (node (ref "U4") (pin "14") (pinfunction "SI_14") (pintype "input"))
    )
    (net (code "28") (name "Net-(B72530T300K62-Pad1)") (class "Default")
      (node (ref "B72530T300K62") (pin "1") (pinfunction "1_1") (pintype "passive"))
      (node (ref "F1") (pin "2") (pinfunction "2_2") (pintype "passive"))
      (node (ref "L1") (pin "1") (pinfunction "1_1") (pintype "passive"))
    )
    (net (code "29") (name "Net-(C34-Pad2)") (class "Default")
      (node (ref "C34") (pin "2") (pinfunction "2_2") (pintype "passive"))
      (node (ref "R10") (pin "1") (pinfunction "1_1") (pintype "passive"))
    )
    (net (code "30") (name "Net-(C35-Pad2)") (class "Default")
      (node (ref "C35") (pin "2") (pinfunction "2_2") (pintype "passive"))
      (node (ref "R12") (pin "1") (pinfunction "1_1") (pintype "passive"))
    )
    (net (code "31") (name "Net-(CF9-Pad3)") (class "Default")
      (node (ref "CF9") (pin "3") (pinfunction "3_3") (pintype "passive"))
      (node (ref "R2") (pin "2") (pinfunction "2_2") (pintype "passive"))
    )
    (net (code "32") (name "Net-(CF10-Pad1)") (class "Default")
      (node (ref "CF10") (pin "1") (pinfunction "1_1") (pintype "passive"))
      (node (ref "R3") (pin "2") (pinfunction "2_2") (pintype "passive"))
    )
    (net (code "33") (name "Net-(IC1-VI)") (class "Default")
      (node (ref "C19") (pin "+") (pinfunction "+_+") (pintype "passive"))
      (node (ref "C20") (pin "+") (pinfunction "+_+") (pintype "passive"))
      (node (ref "D1") (pin "C") (pinfunction "C_C") (pintype "passive"))
      (node (ref "IC1") (pin "1") (pinfunction "VI_1") (pintype "input"))
      (node (ref "L1") (pin "2") (pinfunction "2_2") (pintype "passive"))
    )
    (net (code "34") (name "Net-(IC2-AREF)") (class "Default")
      (node (ref "C30") (pin "1") (pinfunction "1_1") (pintype "passive"))
      (node (ref "IC2") (pin "20") (pinfunction "AREF_20") (pintype "passive"))
    )
    (net (code "35") (name "Net-(IC2-PB6(XTAL1{slash}TOSC1))") (class "Default")
      (node (ref "C28") (pin "1") (pinfunction "1_1") (pintype "passive"))
      (node (ref "IC2") (pin "7") (pinfunction "PB6(XTAL1/TOSC1)_7") (pintype "bidirectional"))
      (node (ref "Q1") (pin "3") (pinfunction "2_3") (pintype "passive"))
    )
    (net (code "36") (name "Net-(IC2-PB7(XTAL2{slash}TOSC2))") (class "Default")
      (node (ref "C29") (pin "1") (pinfunction "1_1") (pintype "passive"))
      (node (ref "IC2") (pin "8") (pinfunction "PB7(XTAL2/TOSC2)_8") (pintype "bidirectional"))
      (node (ref "Q1") (pin "1") (pinfunction "1_1") (pintype "passive"))
    )
    (net (code "37") (name "Net-(Q3-2)") (class "Default")
      (node (ref "C38") (pin "2") (pinfunction "2_2") (pintype "passive"))
      (node (ref "Q3") (pin "3") (pinfunction "2_3") (pintype "passive"))
      (node (ref "U4") (pin "8") (pinfunction "OSC1_8") (pintype "input"))
    )
    (net (code "38") (name "Net-(U$1-A0)") (class "Default")
      (node (ref "CF8") (pin "3") (pinfunction "3_3") (pintype "passive"))
      (node (ref "U$1") (pin "8") (pinfunction "A0_8") (pintype "bidirectional"))
    )
    (net (code "39") (name "Net-(U$1-A1)") (class "Default")
      (node (ref "CF7") (pin "3") (pinfunction "3_3") (pintype "passive"))
      (node (ref "U$1") (pin "7") (pinfunction "A1_7") (pintype "bidirectional"))
    )
    (net (code "40") (name "Net-(U$1-AINN1)") (class "Default")
      (node (ref "C8") (pin "1") (pinfunction "1_1") (pintype "passive"))
      (node (ref "C9") (pin "2") (pinfunction "2_2") (pintype "passive"))
      (node (ref "CF12") (pin "3") (pinfunction "3_3") (pintype "passive"))
      (node (ref "U$1") (pin "12") (pinfunction "AINN1_12") (pintype "bidirectional"))
    )
    (net (code "41") (name "Net-(U$1-AINN2)") (class "Default")
      (node (ref "C11") (pin "1") (pinfunction "1_1") (pintype "passive"))
      (node (ref "C12") (pin "2") (pinfunction "2_2") (pintype "passive"))
      (node (ref "CF14") (pin "3") (pinfunction "3_3") (pintype "passive"))
      (node (ref "U$1") (pin "17") (pinfunction "AINN2_17") (pintype "bidirectional"))
    )
    (net (code "42") (name "Net-(U$1-AINN3)") (class "Default")
      (node (ref "C14") (pin "1") (pinfunction "1_1") (pintype "passive"))
      (node (ref "C15") (pin "2") (pinfunction "2_2") (pintype "passive"))
      (node (ref "CF16") (pin "3") (pinfunction "3_3") (pintype "passive"))
      (node (ref "U$1") (pin "14") (pinfunction "AINN3_14") (pintype "bidirectional"))
    )
    (net (code "43") (name "Net-(U$1-AINN4)") (class "Default")
      (node (ref "C17") (pin "1") (pinfunction "1_1") (pintype "passive"))
      (node (ref "C18") (pin "2") (pinfunction "2_2") (pintype "passive"))
      (node (ref "CF18") (pin "3") (pinfunction "3_3") (pintype "passive"))
      (node (ref "U$1") (pin "15") (pinfunction "AINN4_15") (pintype "bidirectional"))
    )
    (net (code "44") (name "Net-(U$1-AINP1)") (class "Default")
      (node (ref "C7") (pin "2") (pinfunction "2_2") (pintype "passive"))
      (node (ref "C8") (pin "2") (pinfunction "2_2") (pintype "passive"))
      (node (ref "CF11") (pin "1") (pinfunction "1_1") (pintype "passive"))
      (node (ref "U$1") (pin "11") (pinfunction "AINP1_11") (pintype "bidirectional"))
    )
    (net (code "45") (name "Net-(U$1-AINP2)") (class "Default")
      (node (ref "C10") (pin "2") (pinfunction "2_2") (pintype "passive"))
      (node (ref "C11") (pin "2") (pinfunction "2_2") (pintype "passive"))
      (node (ref "CF13") (pin "1") (pinfunction "1_1") (pintype "passive"))
      (node (ref "U$1") (pin "18") (pinfunction "AINP2_18") (pintype "bidirectional"))
    )
    (net (code "46") (name "Net-(U$1-AINP3)") (class "Default")
      (node (ref "C13") (pin "2") (pinfunction "2_2") (pintype "passive"))
      (node (ref "C14") (pin "2") (pinfunction "2_2") (pintype "passive"))
      (node (ref "CF15") (pin "1") (pinfunction "1_1") (pintype "passive"))
      (node (ref "U$1") (pin "13") (pinfunction "AINP3_13") (pintype "bidirectional"))
    )
    (net (code "47") (name "Net-(U$1-AINP4)") (class "Default")
      (node (ref "C16") (pin "2") (pinfunction "2_2") (pintype "passive"))
      (node (ref "C17") (pin "2") (pinfunction "2_2") (pintype "passive"))
      (node (ref "CF17") (pin "1") (pinfunction "1_1") (pintype "passive"))
      (node (ref "U$1") (pin "16") (pinfunction "AINP4_16") (pintype "bidirectional"))
    )
    (net (code "48") (name "Net-(U$1-CAP1)") (class "Default")
      (node (ref "C6") (pin "1") (pinfunction "1_1") (pintype "passive"))
      (node (ref "U$1") (pin "9") (pinfunction "CAP1_9") (pintype "bidirectional"))
    )
    (net (code "49") (name "Net-(U$1-CAP2)") (class "Default")
      (node (ref "C6") (pin "2") (pinfunction "2_2") (pintype "passive"))
      (node (ref "U$1") (pin "10") (pinfunction "CAP2_10") (pintype "bidirectional"))
    )
    (net (code "50") (name "Net-(U$1-CLKIN{slash}XTAL1)") (class "Default")
      (node (ref "R1") (pin "2") (pinfunction "2_2") (pintype "passive"))
      (node (ref "TP2") (pin "TP") (pinfunction "TP_TP") (pintype "input"))
      (node (ref "U$1") (pin "3") (pinfunction "CLKIN/XTAL1_3") (pintype "bidirectional"))
    )
    (net (code "51") (name "Net-(U$1-GAIN0)") (class "Default")
      (node (ref "CF4") (pin "3") (pinfunction "3_3") (pintype "passive"))
      (node (ref "U$1") (pin "23") (pinfunction "GAIN0_23") (pintype "bidirectional"))
    )
    (net (code "52") (name "Net-(U$1-GAIN1)") (class "Default")
      (node (ref "CF5") (pin "3") (pinfunction "3_3") (pintype "passive"))
      (node (ref "U$1") (pin "24") (pinfunction "GAIN1_24") (pintype "bidirectional"))
    )
    (net (code "53") (name "Net-(U$1-REFN)") (class "Default")
      (node (ref "C3") (pin "1") (pinfunction "1_1") (pintype "passive"))
      (node (ref "C4") (pin "2") (pinfunction "2_2") (pintype "passive"))
      (node (ref "CF10") (pin "3") (pinfunction "3_3") (pintype "passive"))
      (node (ref "U$1") (pin "19") (pinfunction "REFN_19") (pintype "bidirectional"))
    )
    (net (code "54") (name "Net-(U$1-REFP)") (class "Default")
      (node (ref "C3") (pin "2") (pinfunction "2_2") (pintype "passive"))
      (node (ref "C5") (pin "2") (pinfunction "2_2") (pintype "passive"))
      (node (ref "CF9") (pin "1") (pinfunction "1_1") (pintype "passive"))
      (node (ref "R4*") (pin "2") (pinfunction "2_2") (pintype "passive"))
      (node (ref "U$1") (pin "20") (pinfunction "REFP_20") (pintype "bidirectional"))
    )
    (net (code "55") (name "Net-(U$1-SCLK)") (class "Default")
      (node (ref "CF2") (pin "3") (pinfunction "3_3") (pintype "passive"))
      (node (ref "U$1") (pin "27") (pinfunction "SCLK_27") (pintype "bidirectional"))
    )
    (net (code "56") (name "Net-(U$1-SPEED)") (class "Default")
      (node (ref "CF3") (pin "3") (pinfunction "3_3") (pintype "passive"))
      (node (ref "U$1") (pin "25") (pinfunction "SPEED_25") (pintype "bidirectional"))
    )
    (net (code "57") (name "Net-(U$1-~{DRDY{slash}}DOUT)") (class "Default")
      (node (ref "CF1") (pin "3") (pinfunction "3_3") (pintype "passive"))
      (node (ref "U$1") (pin "28") (pinfunction "~{DRDY/}DOUT_28") (pintype "bidirectional"))
    )
    (net (code "58") (name "Net-(U$1-~{PDWN})") (class "Default")
      (node (ref "CF6") (pin "3") (pinfunction "3_3") (pintype "passive"))
      (node (ref "U$1") (pin "26") (pinfunction "~{PDWN}_26") (pintype "bidirectional"))
    )
    (net (code "59") (name "Net-(U4A-OSC2)") (class "Default")
      (node (ref "C37") (pin "2") (pinfunction "2_2") (pintype "passive"))
      (node (ref "Q3") (pin "1") (pinfunction "1_1") (pintype "passive"))
      (node (ref "U4") (pin "7") (pinfunction "OSC2_7") (pintype "output"))
    )
    (net (code "60") (name "Net-(U5-RS)") (class "Default")
      (node (ref "R13") (pin "2") (pinfunction "2_2") (pintype "passive"))
      (node (ref "U5") (pin "8") (pinfunction "RS_8") (pintype "bidirectional"))
    )
    (net (code "61") (name "RS") (class "Default")
      (node (ref "R7") (pin "2") (pinfunction "2_2") (pintype "passive"))
      (node (ref "U4") (pin "17") (pinfunction "RESET_17") (pintype "input"))
    )
    (net (code "62") (name "RST") (class "Default")
      (node (ref "IC2") (pin "29") (pinfunction "PC6(/RESET)_29") (pintype "bidirectional"))
      (node (ref "ISP") (pin "5") (pinfunction "5_5") (pintype "passive"))
      (node (ref "R5") (pin "2") (pinfunction "2_2") (pintype "passive"))
    )
    (net (code "63") (name "SCK") (class "Default")
      (node (ref "IC2") (pin "17") (pinfunction "PB5(SCK)_17") (pintype "bidirectional"))
      (node (ref "ISP") (pin "7") (pinfunction "7_7") (pintype "passive"))
      (node (ref "U4") (pin "13") (pinfunction "SCK_13") (pintype "input"))
    )
    (net (code "64") (name "VDD") (class "Default")
      (node (ref "C1") (pin "1") (pinfunction "1_1") (pintype "passive"))
      (node (ref "C21") (pin "+") (pinfunction "+_+") (pintype "passive"))
      (node (ref "C23") (pin "1") (pinfunction "1_1") (pintype "passive"))
      (node (ref "C26") (pin "2") (pinfunction "2_2") (pintype "passive"))
      (node (ref "C27") (pin "1") (pinfunction "1_1") (pintype "passive"))
      (node (ref "C33") (pin "2") (pinfunction "2_2") (pintype "passive"))
      (node (ref "C36") (pin "2") (pinfunction "2_2") (pintype "passive"))
      (node (ref "FERRYT") (pin "1") (pinfunction "1_1") (pintype "passive"))
      (node (ref "IC1") (pin "2") (pinfunction "VO_2") (pintype "passive"))
      (node (ref "IC2") (pin "18") (pinfunction "AVCC_18") (pintype "power_in"))
      (node (ref "IC2") (pin "4") (pinfunction "VCC_4") (pintype "power_in"))
      (node (ref "IC2") (pin "6") (pinfunction "VCC_6") (pintype "power_in"))
      (node (ref "ISP") (pin "10") (pinfunction "10_10") (pintype "passive"))
      (node (ref "R5") (pin "1") (pinfunction "1_1") (pintype "passive"))
      (node (ref "R7") (pin "1") (pinfunction "1_1") (pintype "passive"))
      (node (ref "U$1") (pin "1") (pinfunction "DVDD_1") (pintype "bidirectional"))
      (node (ref "U4") (pin "18") (pinfunction "VDD_18") (pintype "power_in"))
      (node (ref "U5") (pin "3") (pinfunction "VDD_3") (pintype "power_in"))
    )
    (net (code "65") (name "unconnected-(IC2-ADC6-Pad19)") (class "Default")
      (node (ref "IC2") (pin "19") (pinfunction "ADC6_19") (pintype "bidirectional"))
    )
    (net (code "66") (name "unconnected-(IC2-ADC7-Pad22)") (class "Default")
      (node (ref "IC2") (pin "22") (pinfunction "ADC7_22") (pintype "bidirectional"))
    )
    (net (code "67") (name "unconnected-(IC2-PB0(ICP)-Pad12)") (class "Default")
      (node (ref "IC2") (pin "12") (pinfunction "PB0(ICP)_12") (pintype "bidirectional"))
    )
    (net (code "68") (name "unconnected-(IC2-PB1(OC1A)-Pad13)") (class "Default")
      (node (ref "IC2") (pin "13") (pinfunction "PB1(OC1A)_13") (pintype "bidirectional"))
    )
    (net (code "69") (name "unconnected-(IC2-PD0(RXD)-Pad30)") (class "Default")
      (node (ref "IC2") (pin "30") (pinfunction "PD0(RXD)_30") (pintype "bidirectional"))
    )
    (net (code "70") (name "unconnected-(IC2-PD4(XCK{slash}T0)-Pad2)") (class "Default")
      (node (ref "IC2") (pin "2") (pinfunction "PD4(XCK/T0)_2") (pintype "bidirectional"))
    )
    (net (code "71") (name "unconnected-(IC2-PD5(T1)-Pad9)") (class "Default")
      (node (ref "IC2") (pin "9") (pinfunction "PD5(T1)_9") (pintype "bidirectional"))
    )
    (net (code "72") (name "unconnected-(IC2-PD6(AIN0)-Pad10)") (class "Default")
      (node (ref "IC2") (pin "10") (pinfunction "PD6(AIN0)_10") (pintype "bidirectional"))
    )
    (net (code "73") (name "unconnected-(IC2-PD7(AIN1)-Pad11)") (class "Default")
      (node (ref "IC2") (pin "11") (pinfunction "PD7(AIN1)_11") (pintype "bidirectional"))
    )
    (net (code "74") (name "unconnected-(ISP-Pad3)") (class "Default")
      (node (ref "ISP") (pin "3") (pinfunction "3_3") (pintype "passive"))
    )
    (net (code "75") (name "unconnected-(ISP-Pad4)") (class "Default")
      (node (ref "ISP") (pin "4") (pinfunction "4_4") (pintype "passive"))
    )
    (net (code "76") (name "unconnected-(ISP-Pad6)") (class "Default")
      (node (ref "ISP") (pin "6") (pinfunction "6_6") (pintype "passive"))
    )
    (net (code "77") (name "unconnected-(ISP-Pad8)") (class "Default")
      (node (ref "ISP") (pin "8") (pinfunction "8_8") (pintype "passive"))
    )
    (net (code "78") (name "unconnected-(U$1-XTAL2-Pad4)") (class "Default")
      (node (ref "U$1") (pin "4") (pinfunction "XTAL2_4") (pintype "bidirectional"))
    )
    (net (code "79") (name "unconnected-(U4A-CLKOUT-Pad3)") (class "Default")
      (node (ref "U4") (pin "3") (pinfunction "CLKOUT_3") (pintype "output"))
    )
    (net (code "80") (name "unconnected-(U4A-RX0BF-Pad11)") (class "Default")
      (node (ref "U4") (pin "11") (pinfunction "RX0BF_11") (pintype "output"))
    )
    (net (code "81") (name "unconnected-(U4A-RX1BF-Pad10)") (class "Default")
      (node (ref "U4") (pin "10") (pinfunction "RX1BF_10") (pintype "output"))
    )
    (net (code "82") (name "unconnected-(U4A-TX0RTS-Pad4)") (class "Default")
      (node (ref "U4") (pin "4") (pinfunction "TX0RTS_4") (pintype "input"))
    )
    (net (code "83") (name "unconnected-(U4A-TX1RTS-Pad5)") (class "Default")
      (node (ref "U4") (pin "5") (pinfunction "TX1RTS_5") (pintype "input"))
    )
    (net (code "84") (name "unconnected-(U4A-TX2RTS-Pad6)") (class "Default")
      (node (ref "U4") (pin "6") (pinfunction "TX2RTS_6") (pintype "input"))
    )
    (net (code "85") (name "unconnected-(U5-VREF-Pad5)") (class "Default")
      (node (ref "U5") (pin "5") (pinfunction "VREF_5") (pintype "bidirectional"))
    )
  )
)
